# 10_-_CONNECTOR.net
KiCad netlist of a schematic drawn in Altium Designer
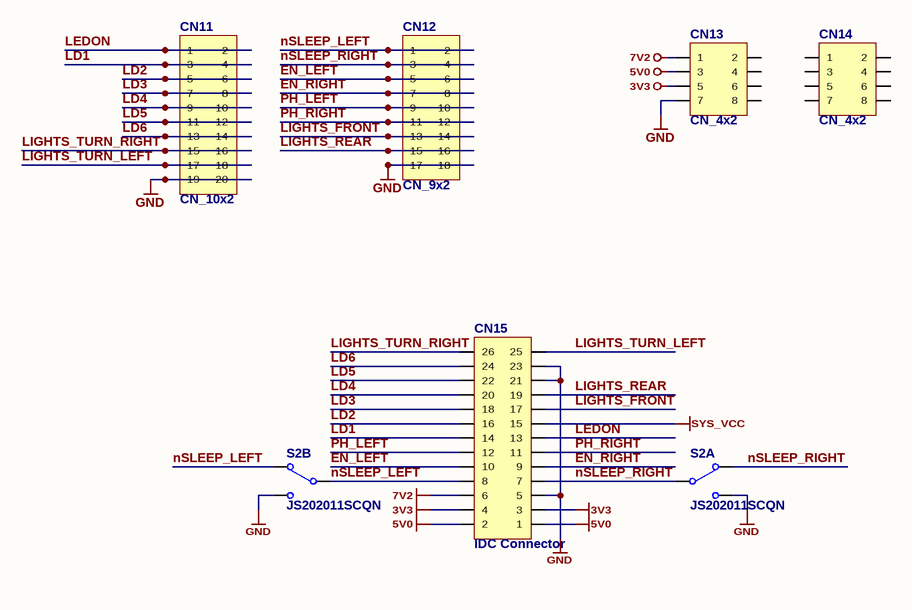
[diagram p0: [10] - CONNECTOR.SchDoc]

(export (version "E")
  (design (tool "Eeschema 10.0.6"))
  (components
    (comp (ref "CN11")
      (value "CN_10x2")
      (footprint "GP_10x2")
      (libsource (lib "goldpin_male") (part "CN_10x2"))
    )
    (comp (ref "CN12") (value "CN_9x2") (footprint "GP_9x2") (libsource (lib "goldpin_male") (part "CN_9x2")))
    (comp (ref "CN13") (value "CN_4x2") (footprint "GP_4x2") (libsource (lib "goldpin_male") (part "CN_4x2")))
    (comp (ref "CN14") (value "CN_4x2") (footprint "GP_4x2") (libsource (lib "goldpin_male") (part "CN_4x2")))
    (comp (ref "CN15")
      (value "IDC Connector")
      (footprint "IDC26_RA")
      (libsource (lib "idc") (part "CN_13x2"))
    )
    (comp (ref "S2")
      (value "JS202011SCQN")
      (footprint "JS202011SCQN")
      (description "C&K JS202011SCQN DPDT Switch")
      (fields (field (name "PUBLISHER") "Altium Limited"))
      (libsource (lib "switches_slide") (part "JS202011SCQN"))
    )
  )
  (nets
    (net (code "1") (name "/EN_LEFT") (class "Default")
      (node (ref "CN12") (pin "5") (pinfunction "5_5") (pintype "passive"))
      (node (ref "CN12") (pin "6") (pinfunction "6_6") (pintype "passive"))
      (node (ref "CN15") (pin "10") (pinfunction "10_10") (pintype "passive"))
    )
    (net (code "2") (name "/EN_RIGHT") (class "Default")
      (node (ref "CN12") (pin "7") (pinfunction "7_7") (pintype "passive"))
      (node (ref "CN12") (pin "8") (pinfunction "8_8") (pintype "passive"))
      (node (ref "CN15") (pin "9") (pinfunction "9_9") (pintype "passive"))
    )
    (net (code "3") (name "/LD1") (class "Default")
      (node (ref "CN11") (pin "3") (pinfunction "3_3") (pintype "passive"))
      (node (ref "CN11") (pin "4") (pinfunction "4_4") (pintype "passive"))
      (node (ref "CN15") (pin "14") (pinfunction "14_14") (pintype "passive"))
    )
    (net (code "4") (name "/LD2") (class "Default")
      (node (ref "CN11") (pin "5") (pinfunction "5_5") (pintype "passive"))
      (node (ref "CN11") (pin "6") (pinfunction "6_6") (pintype "passive"))
      (node (ref "CN15") (pin "16") (pinfunction "16_16") (pintype "passive"))
    )
    (net (code "5") (name "/LD3") (class "Default")
      (node (ref "CN11") (pin "7") (pinfunction "7_7") (pintype "passive"))
      (node (ref "CN11") (pin "8") (pinfunction "8_8") (pintype "passive"))
      (node (ref "CN15") (pin "18") (pinfunction "18_18") (pintype "passive"))
    )
    (net (code "6") (name "/LD4") (class "Default")
      (node (ref "CN11") (pin "10") (pinfunction "10_10") (pintype "passive"))
      (node (ref "CN11") (pin "9") (pinfunction "9_9") (pintype "passive"))
      (node (ref "CN15") (pin "20") (pinfunction "20_20") (pintype "passive"))
    )
    (net (code "7") (name "/LD5") (class "Default")
      (node (ref "CN11") (pin "11") (pinfunction "11_11") (pintype "passive"))
      (node (ref "CN11") (pin "12") (pinfunction "12_12") (pintype "passive"))
      (node (ref "CN15") (pin "22") (pinfunction "22_22") (pintype "passive"))
    )
    (net (code "8") (name "/LD6") (class "Default")
      (node (ref "CN11") (pin "13") (pinfunction "13_13") (pintype "passive"))
      (node (ref "CN11") (pin "14") (pinfunction "14_14") (pintype "passive"))
      (node (ref "CN15") (pin "24") (pinfunction "24_24") (pintype "passive"))
    )
    (net (code "9") (name "/LEDON") (class "Default")
      (node (ref "CN11") (pin "1") (pinfunction "1_1") (pintype "passive"))
      (node (ref "CN11") (pin "2") (pinfunction "2_2") (pintype "passive"))
      (node (ref "CN15") (pin "13") (pinfunction "13_13") (pintype "passive"))
    )
    (net (code "10") (name "/LIGHTS_FRONT") (class "Default")
      (node (ref "CN12") (pin "13") (pinfunction "13_13") (pintype "passive"))
      (node (ref "CN12") (pin "14") (pinfunction "14_14") (pintype "passive"))
      (node (ref "CN15") (pin "17") (pinfunction "17_17") (pintype "passive"))
    )
    (net (code "11") (name "/LIGHTS_REAR") (class "Default")
      (node (ref "CN12") (pin "15") (pinfunction "15_15") (pintype "passive"))
      (node (ref "CN12") (pin "16") (pinfunction "16_16") (pintype "passive"))
      (node (ref "CN15") (pin "19") (pinfunction "19_19") (pintype "passive"))
    )
    (net (code "12") (name "/LIGHTS_TURN_LEFT") (class "Default")
      (node (ref "CN11") (pin "17") (pinfunction "17_17") (pintype "passive"))
      (node (ref "CN11") (pin "18") (pinfunction "18_18") (pintype "passive"))
      (node (ref "CN15") (pin "25") (pinfunction "25_25") (pintype "passive"))
    )
    (net (code "13") (name "/LIGHTS_TURN_RIGHT") (class "Default")
      (node (ref "CN11") (pin "15") (pinfunction "15_15") (pintype "passive"))
      (node (ref "CN11") (pin "16") (pinfunction "16_16") (pintype "passive"))
      (node (ref "CN15") (pin "26") (pinfunction "26_26") (pintype "passive"))
    )
    (net (code "14") (name "/PH_LEFT") (class "Default")
      (node (ref "CN12") (pin "10") (pinfunction "10_10") (pintype "passive"))
      (node (ref "CN12") (pin "9") (pinfunction "9_9") (pintype "passive"))
      (node (ref "CN15") (pin "12") (pinfunction "12_12") (pintype "passive"))
    )
    (net (code "15") (name "/PH_RIGHT") (class "Default")
      (node (ref "CN12") (pin "11") (pinfunction "11_11") (pintype "passive"))
      (node (ref "CN12") (pin "12") (pinfunction "12_12") (pintype "passive"))
      (node (ref "CN15") (pin "11") (pinfunction "11_11") (pintype "passive"))
    )
    (net (code "16") (name "/nSLEEP_LEFT") (class "Default")
      (node (ref "CN12") (pin "1") (pinfunction "1_1") (pintype "passive"))
      (node (ref "CN12") (pin "2") (pinfunction "2_2") (pintype "passive"))
      (node (ref "CN15") (pin "8") (pinfunction "8_8") (pintype "passive"))
      (node (ref "S2") (pin "4") (pinfunction "NC2_4") (pintype "passive"))
      (node (ref "S2") (pin "5") (pinfunction "COMMON2_5") (pintype "passive"))
    )
    (net (code "17") (name "/nSLEEP_RIGHT") (class "Default")
      (node (ref "CN12") (pin "3") (pinfunction "3_3") (pintype "passive"))
      (node (ref "CN12") (pin "4") (pinfunction "4_4") (pintype "passive"))
      (node (ref "CN15") (pin "7") (pinfunction "7_7") (pintype "passive"))
      (node (ref "S2") (pin "1") (pinfunction "COMMON1_1") (pintype "passive"))
      (node (ref "S2") (pin "2") (pinfunction "NC1_2") (pintype "passive"))
    )
    (net (code "18") (name "3V3") (class "Default")
      (node (ref "CN13") (pin "5") (pinfunction "5_5") (pintype "passive"))
      (node (ref "CN15") (pin "3") (pinfunction "3_3") (pintype "passive"))
      (node (ref "CN15") (pin "4") (pinfunction "4_4") (pintype "passive"))
    )
    (net (code "19") (name "5V0") (class "Default")
      (node (ref "CN13") (pin "3") (pinfunction "3_3") (pintype "passive"))
      (node (ref "CN15") (pin "1") (pinfunction "1_1") (pintype "passive"))
      (node (ref "CN15") (pin "2") (pinfunction "2_2") (pintype "passive"))
    )
    (net (code "20") (name "7V2") (class "Default")
      (node (ref "CN13") (pin "1") (pinfunction "1_1") (pintype "passive"))
      (node (ref "CN15") (pin "6") (pinfunction "6_6") (pintype "passive"))
    )
    (net (code "21") (name "GND") (class "Default")
      (node (ref "CN11") (pin "19") (pinfunction "19_19") (pintype "passive"))
      (node (ref "CN11") (pin "20") (pinfunction "20_20") (pintype "passive"))
      (node (ref "CN12") (pin "17") (pinfunction "17_17") (pintype "passive"))
      (node (ref "CN12") (pin "18") (pinfunction "18_18") (pintype "passive"))
      (node (ref "CN13") (pin "7") (pinfunction "7_7") (pintype "passive"))
      (node (ref "CN15") (pin "21") (pinfunction "21_21") (pintype "passive"))
      (node (ref "CN15") (pin "23") (pinfunction "23_23") (pintype "passive"))
      (node (ref "CN15") (pin "5") (pinfunction "5_5") (pintype "passive"))
      (node (ref "S2") (pin "3") (pinfunction "NO1_3") (pintype "passive"))
      (node (ref "S2") (pin "6") (pinfunction "NO2_6") (pintype "passive"))
    )
    (net (code "22") (name "SYS_VCC") (class "Default")
      (node (ref "CN15") (pin "15") (pinfunction "15_15") (pintype "passive"))
    )
    (net (code "23") (name "unconnected-(CN13-Pad2)") (class "Default")
      (node (ref "CN13") (pin "2") (pinfunction "2_2") (pintype "passive"))
    )
    (net (code "24") (name "unconnected-(CN13-Pad4)") (class "Default")
      (node (ref "CN13") (pin "4") (pinfunction "4_4") (pintype "passive"))
    )
    (net (code "25") (name "unconnected-(CN13-Pad6)") (class "Default")
      (node (ref "CN13") (pin "6") (pinfunction "6_6") (pintype "passive"))
    )
    (net (code "26") (name "unconnected-(CN13-Pad8)") (class "Default")
      (node (ref "CN13") (pin "8") (pinfunction "8_8") (pintype "passive"))
    )
    (net (code "27") (name "unconnected-(CN14-Pad1)") (class "Default")
      (node (ref "CN14") (pin "1") (pinfunction "1_1") (pintype "passive"))
    )
    (net (code "28") (name "unconnected-(CN14-Pad2)") (class "Default")
      (node (ref "CN14") (pin "2") (pinfunction "2_2") (pintype "passive"))
    )
    (net (code "29") (name "unconnected-(CN14-Pad3)") (class "Default")
      (node (ref "CN14") (pin "3") (pinfunction "3_3") (pintype "passive"))
    )
    (net (code "30") (name "unconnected-(CN14-Pad4)") (class "Default")
      (node (ref "CN14") (pin "4") (pinfunction "4_4") (pintype "passive"))
    )
    (net (code "31") (name "unconnected-(CN14-Pad5)") (class "Default")
      (node (ref "CN14") (pin "5") (pinfunction "5_5") (pintype "passive"))
    )
    (net (code "32") (name "unconnected-(CN14-Pad6)") (class "Default")
      (node (ref "CN14") (pin "6") (pinfunction "6_6") (pintype "passive"))
    )
    (net (code "33") (name "unconnected-(CN14-Pad7)") (class "Default")
      (node (ref "CN14") (pin "7") (pinfunction "7_7") (pintype "passive"))
    )
    (net (code "34") (name "unconnected-(CN14-Pad8)") (class "Default")
      (node (ref "CN14") (pin "8") (pinfunction "8_8") (pintype "passive"))
    )
  )
)
